# vusbtiny.net
KiCad netlist of a schematic drawn in EAGLE
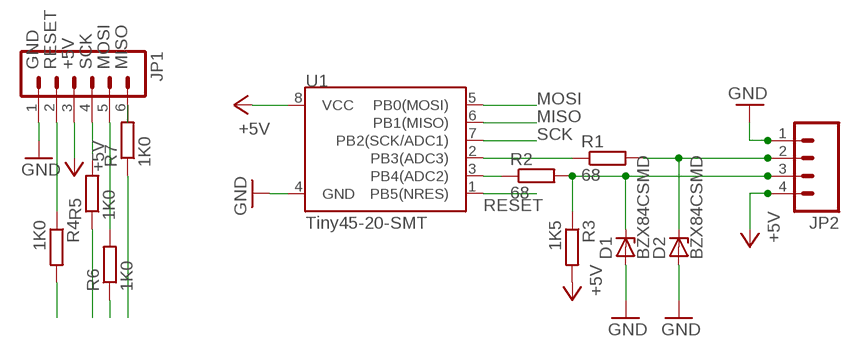
[diagram p0: schematic, sheet 1]

(export (version "E")
  (design (tool "Eeschema 10.0.6"))
  (components
    (comp (ref "D1")
      (value "BZX84CSMD")
      (footprint "eagle-import:TO236")
      (libsource (lib "eagle-import") (part "BZX84CSMD"))
    )
    (comp (ref "D2")
      (value "BZX84CSMD")
      (footprint "eagle-import:TO236")
      (libsource (lib "eagle-import") (part "BZX84CSMD"))
    )
    (comp (ref "JP1")
      (value "M06LONGPADS")
      (footprint "eagle-import:1X06_LONGPADS")
      (libsource (lib "eagle-import") (part "M06LONGPADS"))
    )
    (comp (ref "JP2")
      (value "M04LONGPADS")
      (footprint "eagle-import:1X04_LONGPADS")
      (libsource (lib "eagle-import") (part "M04LONGPADS"))
    )
    (comp (ref "R1")
      (value "68")
      (footprint "eagle-import:R0805")
      (libsource (lib "eagle-import") (part "R-EU_R0805"))
    )
    (comp (ref "R2")
      (value "68")
      (footprint "eagle-import:R0805")
      (libsource (lib "eagle-import") (part "R-EU_R0805"))
    )
    (comp (ref "R3")
      (value "1K5")
      (footprint "eagle-import:R0805")
      (libsource (lib "eagle-import") (part "R-EU_R0805"))
    )
    (comp (ref "R4")
      (value "1K0")
      (footprint "eagle-import:R0805")
      (libsource (lib "eagle-import") (part "R-EU_R0805"))
    )
    (comp (ref "R5")
      (value "1K0")
      (footprint "eagle-import:R0805")
      (libsource (lib "eagle-import") (part "R-EU_R0805"))
    )
    (comp (ref "R6")
      (value "1K0")
      (footprint "eagle-import:R0805")
      (libsource (lib "eagle-import") (part "R-EU_R0805"))
    )
    (comp (ref "R7")
      (value "1K0")
      (footprint "eagle-import:R0805")
      (libsource (lib "eagle-import") (part "R-EU_R0805"))
    )
    (comp (ref "U1")
      (value "Tiny45-20-SMT")
      (footprint "eagle-import:SO08-EIAJ")
      (libsource (lib "eagle-import") (part "ATTINY45TINY45-20-SMT"))
    )
  )
  (nets
    (net (code "1") (name "+5V") (class "Default")
      (node (ref "JP1") (pin "3") (pinfunction "3_3") (pintype "passive"))
      (node (ref "JP2") (pin "4") (pinfunction "4_4") (pintype "passive"))
      (node (ref "R3") (pin "2") (pinfunction "2_2") (pintype "passive"))
      (node (ref "U1") (pin "8") (pinfunction "VCC_8") (pintype "bidirectional"))
    )
    (net (code "2") (name "/MISO") (class "Default")
      (node (ref "R7") (pin "1") (pinfunction "1_1") (pintype "passive"))
      (node (ref "U1") (pin "6") (pinfunction "PB1(MISO)_6") (pintype "bidirectional"))
    )
    (net (code "3") (name "/MOSI") (class "Default")
      (node (ref "R6") (pin "1") (pinfunction "1_1") (pintype "passive"))
      (node (ref "U1") (pin "5") (pinfunction "PB0(MOSI)_5") (pintype "bidirectional"))
    )
    (net (code "4") (name "/RESET") (class "Default")
      (node (ref "R4") (pin "2") (pinfunction "2_2") (pintype "passive"))
      (node (ref "U1") (pin "1") (pinfunction "PB5(NRES)_1") (pintype "bidirectional"))
    )
    (net (code "5") (name "/SCK") (class "Default")
      (node (ref "R5") (pin "1") (pinfunction "1_1") (pintype "passive"))
      (node (ref "U1") (pin "7") (pinfunction "PB2(SCK/ADC1)_7") (pintype "bidirectional"))
    )
    (net (code "6") (name "GND") (class "Default")
      (node (ref "D1") (pin "A") (pinfunction "A_A") (pintype "passive"))
      (node (ref "D2") (pin "A") (pinfunction "A_A") (pintype "passive"))
      (node (ref "JP1") (pin "1") (pinfunction "1_1") (pintype "passive"))
      (node (ref "JP2") (pin "1") (pinfunction "1_1") (pintype "passive"))
      (node (ref "U1") (pin "4") (pinfunction "GND_4") (pintype "bidirectional"))
    )
    (net (code "7") (name "Net-(D1-PadC)") (class "Default")
      (node (ref "D1") (pin "C") (pinfunction "C_C") (pintype "passive"))
      (node (ref "JP2") (pin "3") (pinfunction "3_3") (pintype "passive"))
      (node (ref "R2") (pin "2") (pinfunction "2_2") (pintype "passive"))
      (node (ref "R3") (pin "1") (pinfunction "1_1") (pintype "passive"))
    )
    (net (code "8") (name "Net-(D2-PadC)") (class "Default")
      (node (ref "D2") (pin "C") (pinfunction "C_C") (pintype "passive"))
      (node (ref "JP2") (pin "2") (pinfunction "2_2") (pintype "passive"))
      (node (ref "R1") (pin "2") (pinfunction "2_2") (pintype "passive"))
    )
    (net (code "9") (name "Net-(JP1-Pad2)") (class "Default")
      (node (ref "JP1") (pin "2") (pinfunction "2_2") (pintype "passive"))
      (node (ref "R4") (pin "1") (pinfunction "1_1") (pintype "passive"))
    )
    (net (code "10") (name "Net-(JP1-Pad4)") (class "Default")
      (node (ref "JP1") (pin "4") (pinfunction "4_4") (pintype "passive"))
      (node (ref "R5") (pin "2") (pinfunction "2_2") (pintype "passive"))
    )
    (net (code "11") (name "Net-(JP1-Pad5)") (class "Default")
      (node (ref "JP1") (pin "5") (pinfunction "5_5") (pintype "passive"))
      (node (ref "R6") (pin "2") (pinfunction "2_2") (pintype "passive"))
    )
    (net (code "12") (name "Net-(JP1-Pad6)") (class "Default")
      (node (ref "JP1") (pin "6") (pinfunction "6_6") (pintype "passive"))
      (node (ref "R7") (pin "2") (pinfunction "2_2") (pintype "passive"))
    )
    (net (code "13") (name "Net-(U1-PB3(ADC3))") (class "Default")
      (node (ref "R1") (pin "1") (pinfunction "1_1") (pintype "passive"))
      (node (ref "U1") (pin "2") (pinfunction "PB3(ADC3)_2") (pintype "bidirectional"))
    )
    (net (code "14") (name "Net-(U1-PB4(ADC2))") (class "Default")
      (node (ref "R2") (pin "1") (pinfunction "1_1") (pintype "passive"))
      (node (ref "U1") (pin "3") (pinfunction "PB4(ADC2)_3") (pintype "bidirectional"))
    )
  )
)
